# replacement_pcb_shematic.net
KiCad netlist of a schematic drawn in Altium Designer
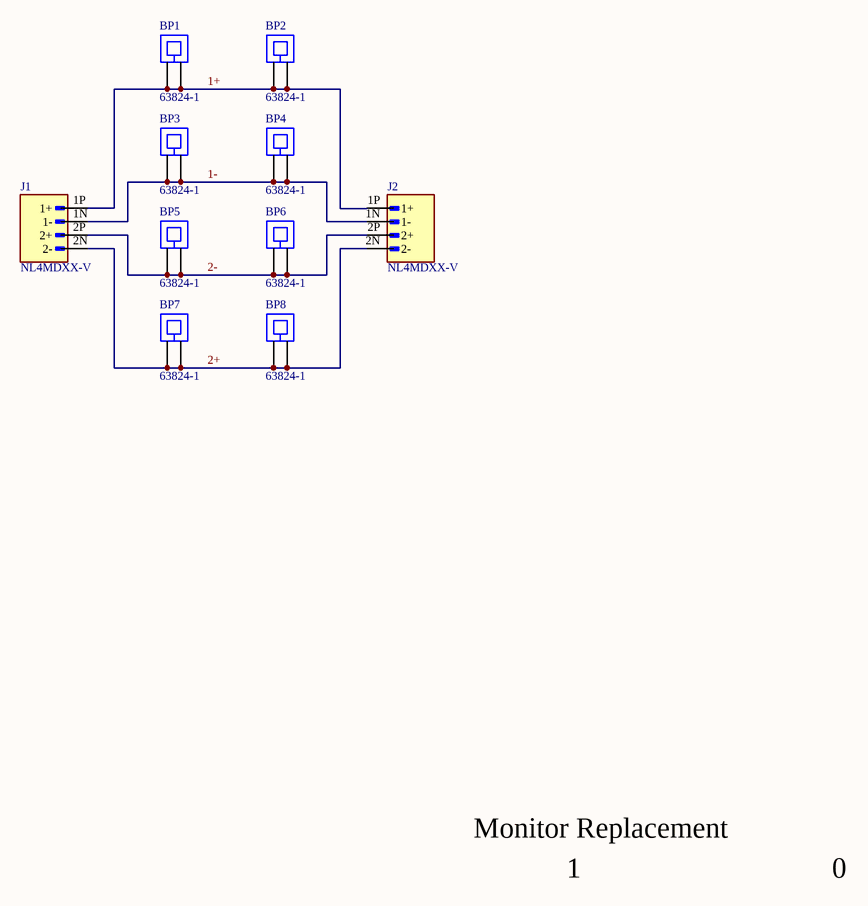
[diagram p0: replacement pcb shematic.SchDoc]

(export (version "E")
  (design (tool "Eeschema 10.0.6"))
  (components
    (comp (ref "BP1")
      (value "63824-1")
      (footprint "TECO-63824-1_V")
      (description "Printed Circuit Board Terminal and Disconnect, 2-Pin THD, RoHS, Tape and Reel")
      (fields (field (name "MANUFACTURER") "TE Connectivity"))
      (libsource (lib "Altium Content Vault") (part "TECO-63824-1"))
    )
    (comp (ref "BP2")
      (value "63824-1")
      (footprint "TECO-63824-1_V")
      (description "Printed Circuit Board Terminal and Disconnect, 2-Pin THD, RoHS, Tape and Reel")
      (fields (field (name "MANUFACTURER") "TE Connectivity"))
      (libsource (lib "Altium Content Vault") (part "TECO-63824-1"))
    )
    (comp (ref "BP3")
      (value "63824-1")
      (footprint "TECO-63824-1_V")
      (description "Printed Circuit Board Terminal and Disconnect, 2-Pin THD, RoHS, Tape and Reel")
      (fields (field (name "MANUFACTURER") "TE Connectivity"))
      (libsource (lib "Altium Content Vault") (part "TECO-63824-1"))
    )
    (comp (ref "BP4")
      (value "63824-1")
      (footprint "TECO-63824-1_V")
      (description "Printed Circuit Board Terminal and Disconnect, 2-Pin THD, RoHS, Tape and Reel")
      (fields (field (name "MANUFACTURER") "TE Connectivity"))
      (libsource (lib "Altium Content Vault") (part "TECO-63824-1"))
    )
    (comp (ref "BP5")
      (value "63824-1")
      (footprint "TECO-63824-1_V")
      (description "Printed Circuit Board Terminal and Disconnect, 2-Pin THD, RoHS, Tape and Reel")
      (fields (field (name "MANUFACTURER") "TE Connectivity"))
      (libsource (lib "Altium Content Vault") (part "TECO-63824-1"))
    )
    (comp (ref "BP6")
      (value "63824-1")
      (footprint "TECO-63824-1_V")
      (description "Printed Circuit Board Terminal and Disconnect, 2-Pin THD, RoHS, Tape and Reel")
      (fields (field (name "MANUFACTURER") "TE Connectivity"))
      (libsource (lib "Altium Content Vault") (part "TECO-63824-1"))
    )
    (comp (ref "BP7")
      (value "63824-1")
      (footprint "TECO-63824-1_V")
      (description "Printed Circuit Board Terminal and Disconnect, 2-Pin THD, RoHS, Tape and Reel")
      (fields (field (name "MANUFACTURER") "TE Connectivity"))
      (libsource (lib "Altium Content Vault") (part "TECO-63824-1"))
    )
    (comp (ref "BP8")
      (value "63824-1")
      (footprint "TECO-63824-1_V")
      (description "Printed Circuit Board Terminal and Disconnect, 2-Pin THD, RoHS, Tape and Reel")
      (fields (field (name "MANUFACTURER") "TE Connectivity"))
      (libsource (lib "Altium Content Vault") (part "TECO-63824-1"))
    )
    (comp (ref "J1")
      (value "NL4MDXX-V")
      (footprint "NEUTRIK_NL4MDXX-V")
      (description "LOUDSPEAKER, PLUG, 4POS, PA6.6, PCB ROHS COMPLIANT: YES")
      (fields (field (name "MF") "NEUTRIK"))
      (libsource (lib "NL4MDXX-V") (part "NL4MDXX-V"))
    )
    (comp (ref "J2")
      (value "NL4MDXX-V")
      (footprint "NEUTRIK_NL4MDXX-V")
      (description "LOUDSPEAKER, PLUG, 4POS, PA6.6, PCB ROHS COMPLIANT: YES")
      (fields (field (name "MF") "NEUTRIK"))
      (libsource (lib "") (part "NL4MDXX-V_1"))
    )
  )
  (nets
    (net (code "1") (name "/1+") (class "Default")
      (node (ref "BP1") (pin "1") (pinfunction "1_1") (pintype "passive"))
      (node (ref "BP1") (pin "2") (pinfunction "2_2") (pintype "passive"))
      (node (ref "BP2") (pin "1") (pinfunction "1_1") (pintype "passive"))
      (node (ref "BP2") (pin "2") (pinfunction "2_2") (pintype "passive"))
      (node (ref "J1") (pin "1P") (pinfunction "1+_1P") (pintype "passive"))
      (node (ref "J2") (pin "1P") (pinfunction "1+_1P") (pintype "passive"))
    )
    (net (code "2") (name "/1-") (class "Default")
      (node (ref "BP3") (pin "1") (pinfunction "1_1") (pintype "passive"))
      (node (ref "BP3") (pin "2") (pinfunction "2_2") (pintype "passive"))
      (node (ref "BP4") (pin "1") (pinfunction "1_1") (pintype "passive"))
      (node (ref "BP4") (pin "2") (pinfunction "2_2") (pintype "passive"))
      (node (ref "J1") (pin "1N") (pinfunction "1-_1N") (pintype "passive"))
      (node (ref "J2") (pin "1N") (pinfunction "1-_1N") (pintype "passive"))
    )
    (net (code "3") (name "/2+") (class "Default")
      (node (ref "BP7") (pin "1") (pinfunction "1_1") (pintype "passive"))
      (node (ref "BP7") (pin "2") (pinfunction "2_2") (pintype "passive"))
      (node (ref "BP8") (pin "1") (pinfunction "1_1") (pintype "passive"))
      (node (ref "BP8") (pin "2") (pinfunction "2_2") (pintype "passive"))
      (node (ref "J1") (pin "2N") (pinfunction "2-_2N") (pintype "passive"))
      (node (ref "J2") (pin "2N") (pinfunction "2-_2N") (pintype "passive"))
    )
    (net (code "4") (name "/2-") (class "Default")
      (node (ref "BP5") (pin "1") (pinfunction "1_1") (pintype "passive"))
      (node (ref "BP5") (pin "2") (pinfunction "2_2") (pintype "passive"))
      (node (ref "BP6") (pin "1") (pinfunction "1_1") (pintype "passive"))
      (node (ref "BP6") (pin "2") (pinfunction "2_2") (pintype "passive"))
      (node (ref "J1") (pin "2P") (pinfunction "2+_2P") (pintype "passive"))
      (node (ref "J2") (pin "2P") (pinfunction "2+_2P") (pintype "passive"))
    )
  )
)
